# SPIDER_ROBOT_1.net
KiCad netlist of a schematic drawn in Altium Designer
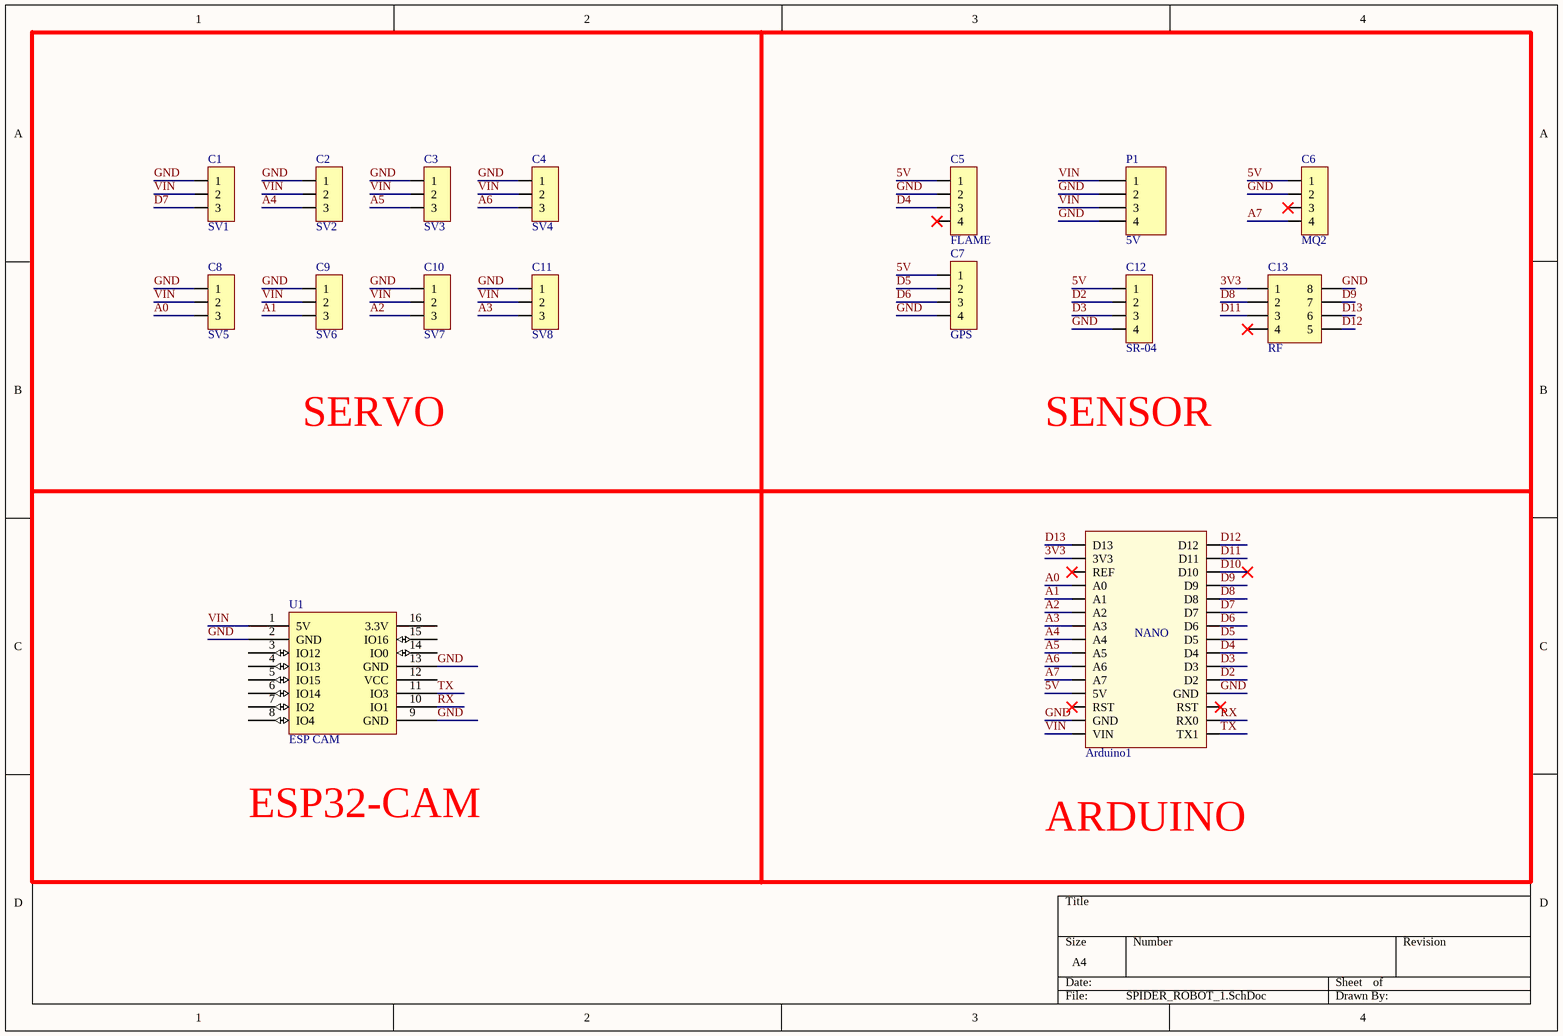
[diagram p0: SPIDER_ROBOT_1.SchDoc]

(export (version "E")
  (design (tool "Eeschema 10.0.6"))
  (components
    (comp (ref "Arduino1")
      (value "Arduino Nano")
      (footprint "Arduino Nano")
      (description "Arduino NANO")
      (libsource (lib "[Eryson]_Library") (part "Arduino Nano"))
    )
    (comp (ref "C1")
      (value "SV1")
      (footprint "JP3-D1T")
      (description "WR-PHD 2.54 mm Angled Socket Header")
      (fields
        (field (name "MANUFACTURER") "Würth Elektronik eiSos GmbH")
        (field (name "PARTNO") "613003143121")
        (field (name "CREATED BY") "Karrer Zheng")
      )
      (libsource (lib "[Eryson]_Library") (part "JP3"))
    )
    (comp (ref "C2")
      (value "SV2")
      (footprint "JP3-D1T")
      (description "WR-PHD 2.54 mm Angled Socket Header")
      (fields
        (field (name "MANUFACTURER") "Würth Elektronik eiSos GmbH")
        (field (name "PARTNO") "613003143121")
        (field (name "CREATED BY") "Karrer Zheng")
      )
      (libsource (lib "[Eryson]_Library") (part "JP3"))
    )
    (comp (ref "C3")
      (value "SV3")
      (footprint "JP3-D1T")
      (description "WR-PHD 2.54 mm Angled Socket Header")
      (fields
        (field (name "MANUFACTURER") "Würth Elektronik eiSos GmbH")
        (field (name "PARTNO") "613003143121")
        (field (name "CREATED BY") "Karrer Zheng")
      )
      (libsource (lib "[Eryson]_Library") (part "JP3"))
    )
    (comp (ref "C4")
      (value "SV4")
      (footprint "JP3-D1T")
      (description "WR-PHD 2.54 mm Angled Socket Header")
      (fields
        (field (name "MANUFACTURER") "Würth Elektronik eiSos GmbH")
        (field (name "PARTNO") "613003143121")
        (field (name "CREATED BY") "Karrer Zheng")
      )
      (libsource (lib "[Eryson]_Library") (part "JP3"))
    )
    (comp (ref "C5")
      (value "FLAME")
      (footprint "JP4-C1T")
      (description "WR-PHD 2.54 mm Angled Socket Header")
      (fields
        (field (name "MANUFACTURER") "Würth Elektronik eiSos GmbH")
        (field (name "PARTNO") "613004143121")
        (field (name "CREATED BY") "Karrer Zheng")
      )
      (libsource (lib "[Eryson]_Library") (part "JP4"))
    )
    (comp (ref "C6")
      (value "MQ2")
      (footprint "JP4-C1T")
      (description "WR-PHD 2.54 mm Angled Socket Header")
      (fields
        (field (name "MANUFACTURER") "Würth Elektronik eiSos GmbH")
        (field (name "PARTNO") "613004143121")
        (field (name "CREATED BY") "Karrer Zheng")
      )
      (libsource (lib "[Eryson]_Library") (part "JP4"))
    )
    (comp (ref "C7")
      (value "GPS")
      (footprint "JP4-C1T")
      (description "WR-PHD 2.54 mm Angled Socket Header")
      (fields
        (field (name "MANUFACTURER") "Würth Elektronik eiSos GmbH")
        (field (name "PARTNO") "613004143121")
        (field (name "CREATED BY") "Karrer Zheng")
      )
      (libsource (lib "[Eryson]_Library") (part "JP4"))
    )
    (comp (ref "C8")
      (value "SV5")
      (footprint "JP3-D1T")
      (description "WR-PHD 2.54 mm Angled Socket Header")
      (fields
        (field (name "MANUFACTURER") "Würth Elektronik eiSos GmbH")
        (field (name "PARTNO") "613003143121")
        (field (name "CREATED BY") "Karrer Zheng")
      )
      (libsource (lib "[Eryson]_Library") (part "JP3"))
    )
    (comp (ref "C9")
      (value "SV6")
      (footprint "JP3-D1T")
      (description "WR-PHD 2.54 mm Angled Socket Header")
      (fields
        (field (name "MANUFACTURER") "Würth Elektronik eiSos GmbH")
        (field (name "PARTNO") "613003143121")
        (field (name "CREATED BY") "Karrer Zheng")
      )
      (libsource (lib "[Eryson]_Library") (part "JP3"))
    )
    (comp (ref "C10")
      (value "SV7")
      (footprint "JP3-D1T")
      (description "WR-PHD 2.54 mm Angled Socket Header")
      (fields
        (field (name "MANUFACTURER") "Würth Elektronik eiSos GmbH")
        (field (name "PARTNO") "613003143121")
        (field (name "CREATED BY") "Karrer Zheng")
      )
      (libsource (lib "[Eryson]_Library") (part "JP3"))
    )
    (comp (ref "C11")
      (value "SV8")
      (footprint "JP3-D1T")
      (description "WR-PHD 2.54 mm Angled Socket Header")
      (fields
        (field (name "MANUFACTURER") "Würth Elektronik eiSos GmbH")
        (field (name "PARTNO") "613003143121")
        (field (name "CREATED BY") "Karrer Zheng")
      )
      (libsource (lib "[Eryson]_Library") (part "JP3"))
    )
    (comp (ref "C12")
      (value "SR-04")
      (footprint "JP4-C1T")
      (description "WR-PHD 2.54 mm Angled Socket Header")
      (fields
        (field (name "MANUFACTURER") "Würth Elektronik eiSos GmbH")
        (field (name "PARTNO") "613004143121")
        (field (name "CREATED BY") "Karrer Zheng")
      )
      (libsource (lib "[Eryson]_Library") (part "JP4"))
    )
    (comp (ref "C13")
      (value "RF")
      (footprint "JP4-C2T")
      (description "WR-PHD 2.54 mm Dual Socket Header")
      (fields
        (field (name "MANUFACTURER") "Würth Elektronik eiSos GmbH")
        (field (name "PARTNO") "61300821821")
        (field (name "CREATED BY") "Karrer Zheng")
      )
      (libsource (lib "[Eryson]_Library") (part "JP4x2"))
    )
    (comp (ref "P1")
      (value "5V")
      (footprint "DOMINO_4P_2.54MM")
      (libsource (lib "[Eryson]_Library") (part "Domino 4 pin"))
    )
    (comp (ref "U1")
      (value "ESP CAM")
      (footprint "ESP32_CAM")
      (description "ESP-12 Wi-Fi Module by AI-Thinker")
      (libsource (lib "[Eryson]_Library") (part "ESP32_CAM"))
    )
  )
  (nets
    (net (code "1") (name "/3V3") (class "Default")
      (node (ref "Arduino1") (pin "3V3") (pinfunction "3V3_3V3") (pintype "passive"))
      (node (ref "C13") (pin "1") (pinfunction "1_1") (pintype "passive"))
    )
    (net (code "2") (name "/5V") (class "Default")
      (node (ref "Arduino1") (pin "5V") (pinfunction "5V_5V") (pintype "passive"))
      (node (ref "C12") (pin "1") (pinfunction "1_1") (pintype "passive"))
      (node (ref "C5") (pin "1") (pinfunction "1_1") (pintype "passive"))
      (node (ref "C6") (pin "1") (pinfunction "1_1") (pintype "passive"))
      (node (ref "C7") (pin "1") (pinfunction "1_1") (pintype "passive"))
    )
    (net (code "3") (name "/A0") (class "Default")
      (node (ref "Arduino1") (pin "A0") (pinfunction "A0_A0") (pintype "passive"))
      (node (ref "C8") (pin "3") (pinfunction "3_3") (pintype "passive"))
    )
    (net (code "4") (name "/A1") (class "Default")
      (node (ref "Arduino1") (pin "A1") (pinfunction "A1_A1") (pintype "passive"))
      (node (ref "C9") (pin "3") (pinfunction "3_3") (pintype "passive"))
    )
    (net (code "5") (name "/A2") (class "Default")
      (node (ref "Arduino1") (pin "A2") (pinfunction "A2_A2") (pintype "passive"))
      (node (ref "C10") (pin "3") (pinfunction "3_3") (pintype "passive"))
    )
    (net (code "6") (name "/A3") (class "Default")
      (node (ref "Arduino1") (pin "A3") (pinfunction "A3_A3") (pintype "passive"))
      (node (ref "C11") (pin "3") (pinfunction "3_3") (pintype "passive"))
    )
    (net (code "7") (name "/A4") (class "Default")
      (node (ref "Arduino1") (pin "A4") (pinfunction "A4_A4") (pintype "passive"))
      (node (ref "C2") (pin "3") (pinfunction "3_3") (pintype "passive"))
    )
    (net (code "8") (name "/A5") (class "Default")
      (node (ref "Arduino1") (pin "A5") (pinfunction "A5_A5") (pintype "passive"))
      (node (ref "C3") (pin "3") (pinfunction "3_3") (pintype "passive"))
    )
    (net (code "9") (name "/A6") (class "Default")
      (node (ref "Arduino1") (pin "A6") (pinfunction "A6_A6") (pintype "passive"))
      (node (ref "C4") (pin "3") (pinfunction "3_3") (pintype "passive"))
    )
    (net (code "10") (name "/A7") (class "Default")
      (node (ref "Arduino1") (pin "A7") (pinfunction "A7_A7") (pintype "passive"))
      (node (ref "C6") (pin "4") (pinfunction "4_4") (pintype "passive"))
    )
    (net (code "11") (name "/D2") (class "Default")
      (node (ref "Arduino1") (pin "D2") (pinfunction "D2_D2") (pintype "passive"))
      (node (ref "C12") (pin "2") (pinfunction "2_2") (pintype "passive"))
    )
    (net (code "12") (name "/D3") (class "Default")
      (node (ref "Arduino1") (pin "D3") (pinfunction "D3_D3") (pintype "passive"))
      (node (ref "C12") (pin "3") (pinfunction "3_3") (pintype "passive"))
    )
    (net (code "13") (name "/D4") (class "Default")
      (node (ref "Arduino1") (pin "D4") (pinfunction "D4_D4") (pintype "passive"))
      (node (ref "C5") (pin "3") (pinfunction "3_3") (pintype "passive"))
    )
    (net (code "14") (name "/D5") (class "Default")
      (node (ref "Arduino1") (pin "D5") (pinfunction "D5_D5") (pintype "passive"))
      (node (ref "C7") (pin "2") (pinfunction "2_2") (pintype "passive"))
    )
    (net (code "15") (name "/D6") (class "Default")
      (node (ref "Arduino1") (pin "D6") (pinfunction "D6_D6") (pintype "passive"))
      (node (ref "C7") (pin "3") (pinfunction "3_3") (pintype "passive"))
    )
    (net (code "16") (name "/D7") (class "Default")
      (node (ref "Arduino1") (pin "D7") (pinfunction "D7_D7") (pintype "passive"))
      (node (ref "C1") (pin "3") (pinfunction "3_3") (pintype "passive"))
    )
    (net (code "17") (name "/D8") (class "Default")
      (node (ref "Arduino1") (pin "D8") (pinfunction "D8_D8") (pintype "passive"))
      (node (ref "C13") (pin "2") (pinfunction "2_2") (pintype "passive"))
    )
    (net (code "18") (name "/D9") (class "Default")
      (node (ref "Arduino1") (pin "D9") (pinfunction "D9_D9") (pintype "passive"))
      (node (ref "C13") (pin "7") (pinfunction "7_7") (pintype "passive"))
    )
    (net (code "19") (name "/D10") (class "Default")
      (node (ref "Arduino1") (pin "D10") (pinfunction "D10_D10") (pintype "passive+no_connect"))
    )
    (net (code "20") (name "/D11") (class "Default")
      (node (ref "Arduino1") (pin "D11") (pinfunction "D11_D11") (pintype "passive"))
      (node (ref "C13") (pin "3") (pinfunction "3_3") (pintype "passive"))
    )
    (net (code "21") (name "/D12") (class "Default")
      (node (ref "Arduino1") (pin "D12") (pinfunction "D12_D12") (pintype "passive"))
      (node (ref "C13") (pin "5") (pinfunction "5_5") (pintype "passive"))
    )
    (net (code "22") (name "/D13") (class "Default")
      (node (ref "Arduino1") (pin "D13") (pinfunction "D13_D13") (pintype "passive"))
      (node (ref "C13") (pin "6") (pinfunction "6_6") (pintype "passive"))
    )
    (net (code "23") (name "/GND") (class "Default")
      (node (ref "Arduino1") (pin "GND") (pinfunction "GND_GND") (pintype "passive"))
      (node (ref "C1") (pin "1") (pinfunction "1_1") (pintype "passive"))
      (node (ref "C10") (pin "1") (pinfunction "1_1") (pintype "passive"))
      (node (ref "C11") (pin "1") (pinfunction "1_1") (pintype "passive"))
      (node (ref "C12") (pin "4") (pinfunction "4_4") (pintype "passive"))
      (node (ref "C13") (pin "8") (pinfunction "8_8") (pintype "passive"))
      (node (ref "C2") (pin "1") (pinfunction "1_1") (pintype "passive"))
      (node (ref "C3") (pin "1") (pinfunction "1_1") (pintype "passive"))
      (node (ref "C4") (pin "1") (pinfunction "1_1") (pintype "passive"))
      (node (ref "C5") (pin "2") (pinfunction "2_2") (pintype "passive"))
      (node (ref "C6") (pin "2") (pinfunction "2_2") (pintype "passive"))
      (node (ref "C7") (pin "4") (pinfunction "4_4") (pintype "passive"))
      (node (ref "C8") (pin "1") (pinfunction "1_1") (pintype "passive"))
      (node (ref "C9") (pin "1") (pinfunction "1_1") (pintype "passive"))
      (node (ref "P1") (pin "2") (pinfunction "2_2") (pintype "passive"))
      (node (ref "P1") (pin "4") (pinfunction "4_4") (pintype "passive"))
      (node (ref "U1") (pin "13") (pinfunction "GND_13") (pintype "power_in"))
      (node (ref "U1") (pin "2") (pinfunction "GND_2") (pintype "power_in"))
      (node (ref "U1") (pin "9") (pinfunction "GND_9") (pintype "power_in"))
    )
    (net (code "24") (name "/RX") (class "Default")
      (node (ref "Arduino1") (pin "RX0") (pinfunction "RX0_RX0") (pintype "passive"))
      (node (ref "U1") (pin "10") (pinfunction "IO1_10") (pintype "passive"))
    )
    (net (code "25") (name "/TX") (class "Default")
      (node (ref "Arduino1") (pin "TX1") (pinfunction "TX1_TX1") (pintype "passive"))
      (node (ref "U1") (pin "11") (pinfunction "IO3_11") (pintype "passive"))
    )
    (net (code "26") (name "/VIN") (class "Default")
      (node (ref "Arduino1") (pin "VIN") (pinfunction "VIN_VIN") (pintype "passive"))
      (node (ref "C1") (pin "2") (pinfunction "2_2") (pintype "passive"))
      (node (ref "C10") (pin "2") (pinfunction "2_2") (pintype "passive"))
      (node (ref "C11") (pin "2") (pinfunction "2_2") (pintype "passive"))
      (node (ref "C2") (pin "2") (pinfunction "2_2") (pintype "passive"))
      (node (ref "C3") (pin "2") (pinfunction "2_2") (pintype "passive"))
      (node (ref "C4") (pin "2") (pinfunction "2_2") (pintype "passive"))
      (node (ref "C8") (pin "2") (pinfunction "2_2") (pintype "passive"))
      (node (ref "C9") (pin "2") (pinfunction "2_2") (pintype "passive"))
      (node (ref "P1") (pin "1") (pinfunction "1_1") (pintype "passive"))
      (node (ref "P1") (pin "3") (pinfunction "3_3") (pintype "passive"))
      (node (ref "U1") (pin "1") (pinfunction "5V_1") (pintype "power_in"))
    )
    (net (code "27") (name "unconnected-(Arduino1-PadREF)") (class "Default")
      (node (ref "Arduino1") (pin "REF") (pinfunction "REF_REF") (pintype "passive+no_connect"))
    )
    (net (code "28") (name "unconnected-(Arduino1-PadRST)") (class "Default")
      (node (ref "Arduino1") (pin "RST") (pinfunction "RST_RST") (pintype "passive+no_connect"))
    )
    (net (code "29") (name "unconnected-(Arduino1-PadRST)_1") (class "Default")
      (node (ref "Arduino1") (pin "RST") (pinfunction "RST_RST") (pintype "passive+no_connect"))
    )
    (net (code "30") (name "unconnected-(C5-Pad4)") (class "Default")
      (node (ref "C5") (pin "4") (pinfunction "4_4") (pintype "passive+no_connect"))
    )
    (net (code "31") (name "unconnected-(C6-Pad3)") (class "Default")
      (node (ref "C6") (pin "3") (pinfunction "3_3") (pintype "passive+no_connect"))
    )
    (net (code "32") (name "unconnected-(C13-Pad4)") (class "Default")
      (node (ref "C13") (pin "4") (pinfunction "4_4") (pintype "passive+no_connect"))
    )
    (net (code "33") (name "unconnected-(U1-3.3V-Pad16)") (class "Default")
      (node (ref "U1") (pin "16") (pinfunction "3.3V_16") (pintype "power_in"))
    )
    (net (code "34") (name "unconnected-(U1-IO0-Pad14)") (class "Default")
      (node (ref "U1") (pin "14") (pinfunction "IO0_14") (pintype "bidirectional"))
    )
    (net (code "35") (name "unconnected-(U1-IO2-Pad7)") (class "Default")
      (node (ref "U1") (pin "7") (pinfunction "IO2_7") (pintype "bidirectional"))
    )
    (net (code "36") (name "unconnected-(U1-IO4-Pad8)") (class "Default")
      (node (ref "U1") (pin "8") (pinfunction "IO4_8") (pintype "bidirectional"))
    )
    (net (code "37") (name "unconnected-(U1-IO12-Pad3)") (class "Default")
      (node (ref "U1") (pin "3") (pinfunction "IO12_3") (pintype "bidirectional"))
    )
    (net (code "38") (name "unconnected-(U1-IO13-Pad4)") (class "Default")
      (node (ref "U1") (pin "4") (pinfunction "IO13_4") (pintype "bidirectional"))
    )
    (net (code "39") (name "unconnected-(U1-IO14-Pad6)") (class "Default")
      (node (ref "U1") (pin "6") (pinfunction "IO14_6") (pintype "bidirectional"))
    )
    (net (code "40") (name "unconnected-(U1-IO15-Pad5)") (class "Default")
      (node (ref "U1") (pin "5") (pinfunction "IO15_5") (pintype "bidirectional"))
    )
    (net (code "41") (name "unconnected-(U1-IO16-Pad15)") (class "Default")
      (node (ref "U1") (pin "15") (pinfunction "IO16_15") (pintype "bidirectional"))
    )
    (net (code "42") (name "unconnected-(U1-VCC-Pad12)") (class "Default")
      (node (ref "U1") (pin "12") (pinfunction "VCC_12") (pintype "power_in"))
    )
  )
)
